# 2022-SS-ZT-2.net
KiCad netlist of a schematic drawn in EasyEDA Pro
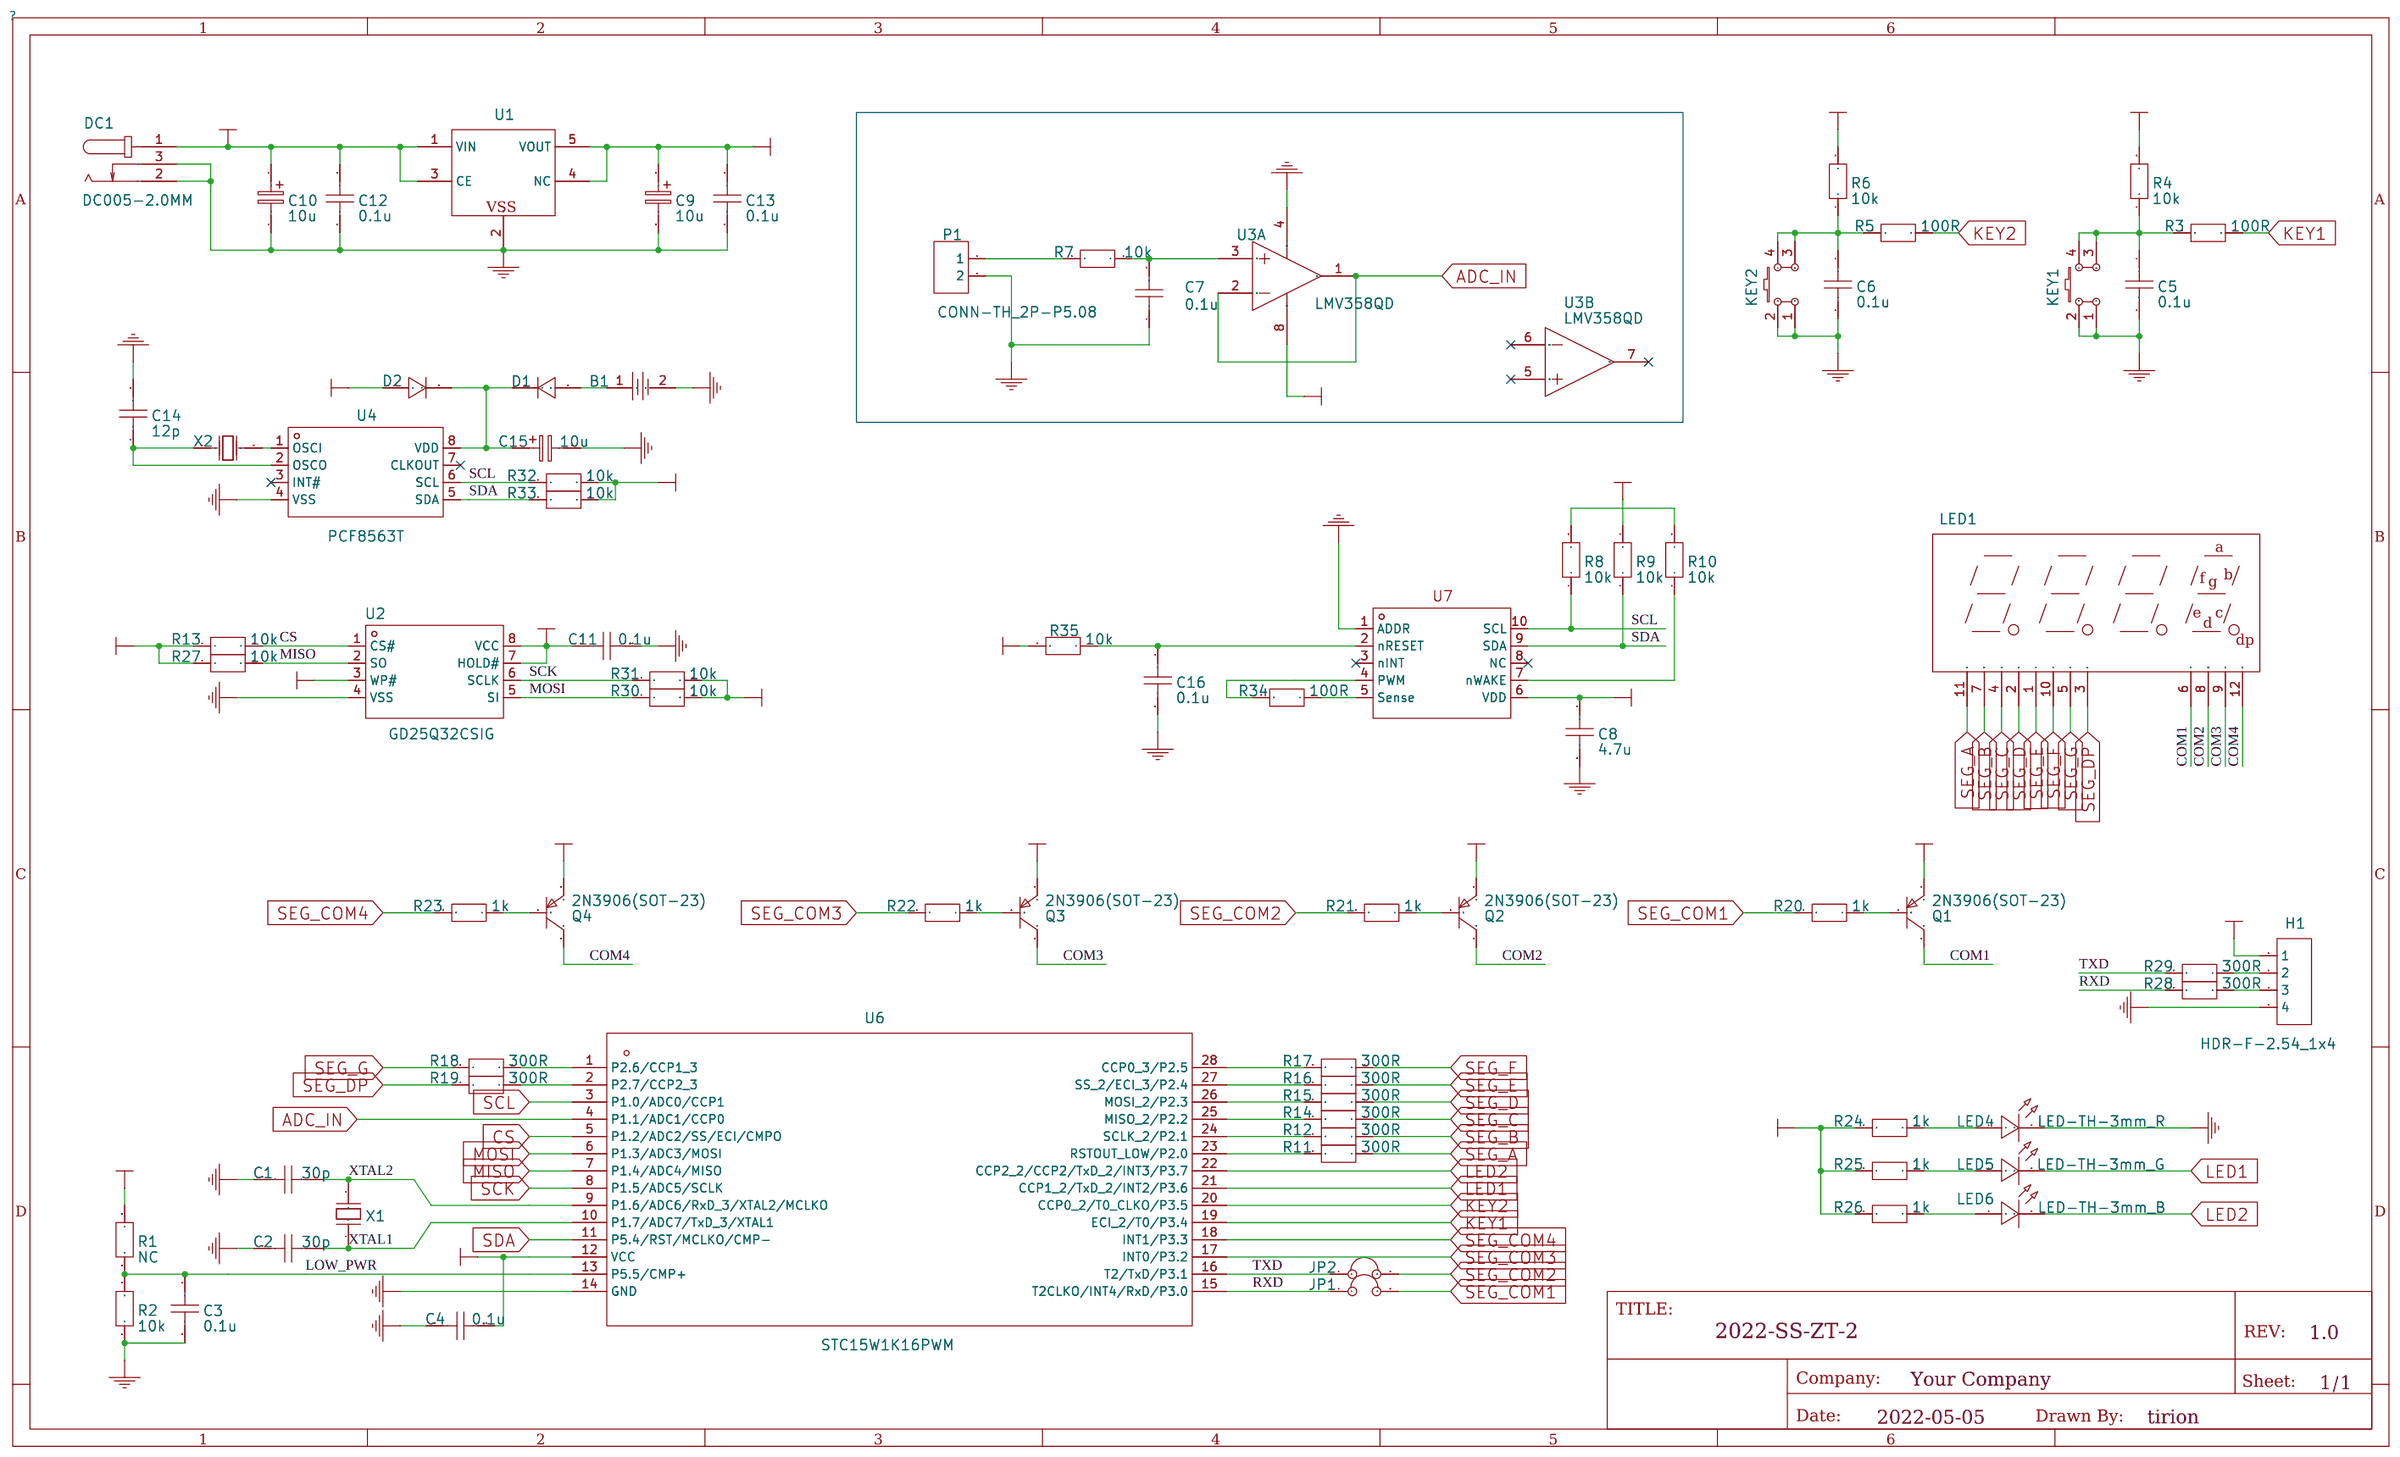
[diagram p0: schematic sheet]

(export (version "E")
  (design (tool "Eeschema 10.0.6"))
  (components
    (comp (ref "B1")
      (value "CR1220-2")
      (fields (field (name "Manufacturer") "Q&amp;J"))
      (libsource (lib "easyedapro") (part "CR1220-2"))
    )
    (comp (ref "C1") (value "30p") (libsource (lib "easyedapro") (part "30p")))
    (comp (ref "C2") (value "30p") (libsource (lib "easyedapro") (part "30p")))
    (comp (ref "C3") (value "0.1u") (libsource (lib "easyedapro") (part "0.1u")))
    (comp (ref "C4") (value "0.1u") (libsource (lib "easyedapro") (part "0.1u")))
    (comp (ref "C5") (value "0.1u") (libsource (lib "easyedapro") (part "0.1u")))
    (comp (ref "C6") (value "0.1u") (libsource (lib "easyedapro") (part "0.1u")))
    (comp (ref "C7") (value "0.1u") (libsource (lib "easyedapro") (part "0.1u")))
    (comp (ref "C8") (value "4.7u") (libsource (lib "easyedapro") (part "4.7u")))
    (comp (ref "C9") (value "10u") (libsource (lib "easyedapro") (part "10u")))
    (comp (ref "C10") (value "10u") (libsource (lib "easyedapro") (part "10u")))
    (comp (ref "C11") (value "0.1u") (libsource (lib "easyedapro") (part "0.1u")))
    (comp (ref "C12") (value "0.1u") (libsource (lib "easyedapro") (part "0.1u")))
    (comp (ref "C13") (value "0.1u") (libsource (lib "easyedapro") (part "0.1u")))
    (comp (ref "C14") (value "12p") (libsource (lib "easyedapro") (part "12p")))
    (comp (ref "C15") (value "10u") (libsource (lib "easyedapro") (part "10u")))
    (comp (ref "C16") (value "0.1u") (libsource (lib "easyedapro") (part "0.1u")))
    (comp (ref "D1")
      (value "1N4148")
      (fields (field (name "Manufacturer") "STMicroelectronics"))
      (libsource (lib "easyedapro") (part "1N4148"))
    )
    (comp (ref "D2")
      (value "1N4148")
      (fields (field (name "Manufacturer") "STMicroelectronics"))
      (libsource (lib "easyedapro") (part "1N4148"))
    )
    (comp (ref "DC1")
      (value "DC005-2.0MM")
      (fields (field (name "Manufacturer") "SOFNG"))
      (libsource (lib "easyedapro") (part "DC005-2.0MM"))
    )
    (comp (ref "H1") (value "HDR-F-2.54_1x4") (libsource (lib "easyedapro") (part "HDR-F-2.54_1x4")))
    (comp (ref "JP1") (value "跳线") (libsource (lib "easyedapro") (part "跳线")))
    (comp (ref "JP2") (value "跳线") (libsource (lib "easyedapro") (part "跳线")))
    (comp (ref "KEY1")
      (value "K4-6×6_SMD")
      (fields (field (name "Manufacturer Part") "K2-6639SP-D4SC-04") (field (name "Manufacturer") "韩国韩荣"))
      (libsource (lib "easyedapro") (part "K4-6×6_SMD"))
    )
    (comp (ref "KEY2")
      (value "K4-6×6_SMD")
      (fields (field (name "Manufacturer Part") "K2-6639SP-D4SC-04") (field (name "Manufacturer") "韩国韩荣"))
      (libsource (lib "easyedapro") (part "K4-6×6_SMD"))
    )
    (comp (ref "LED1")
      (value "0.36寸4位数码管")
      (fields (field (name "Manufacturer Part") "FJ5461BH 纯红") (field (name "Manufacturer") "ReliaPro"))
      (libsource (lib "easyedapro") (part "0.36寸4位数码管"))
    )
    (comp (ref "LED4")
      (value "LED-TH-3mm_R")
      (fields
        (field (name "Manufacturer Part") "204-10SDRD/S530-A3-L")
        (field (name "Manufacturer") "EVERLIGHT(台湾亿光)")
      )
      (libsource (lib "easyedapro") (part "LED-TH-3mm_R"))
    )
    (comp (ref "LED5")
      (value "LED-TH-3mm_G")
      (fields
        (field (name "Manufacturer Part") "204-10SYGD/S530-E3")
        (field (name "Manufacturer") "EVERLIGHT(台湾亿光)")
      )
      (libsource (lib "easyedapro") (part "LED-TH-3mm_G"))
    )
    (comp (ref "LED6")
      (value "LED-TH-3mm_B")
      (fields
        (field (name "Manufacturer Part") "204-10SUBC/S400-A4")
        (field (name "Manufacturer") "EVERLIGHT(台湾亿光)")
      )
      (libsource (lib "easyedapro") (part "LED-TH-3mm_B"))
    )
    (comp (ref "P1") (value "CONN-TH_2P-P5.08") (libsource (lib "easyedapro") (part "CONN-TH_2P-P5.08")))
    (comp (ref "Q1")
      (value "2N3906(SOT-23)")
      (fields (field (name "Manufacturer Part") "2N3906S-RTK/PS") (field (name "Manufacturer") "KEC"))
      (libsource (lib "easyedapro") (part "2N3906(SOT-23)"))
    )
    (comp (ref "Q2")
      (value "2N3906(SOT-23)")
      (fields (field (name "Manufacturer Part") "2N3906S-RTK/PS") (field (name "Manufacturer") "KEC"))
      (libsource (lib "easyedapro") (part "2N3906(SOT-23)"))
    )
    (comp (ref "Q3")
      (value "2N3906(SOT-23)")
      (fields (field (name "Manufacturer Part") "2N3906S-RTK/PS") (field (name "Manufacturer") "KEC"))
      (libsource (lib "easyedapro") (part "2N3906(SOT-23)"))
    )
    (comp (ref "Q4")
      (value "2N3906(SOT-23)")
      (fields (field (name "Manufacturer Part") "2N3906S-RTK/PS") (field (name "Manufacturer") "KEC"))
      (libsource (lib "easyedapro") (part "2N3906(SOT-23)"))
    )
    (comp (ref "R1") (value "NC") (libsource (lib "easyedapro") (part "NC")))
    (comp (ref "R2") (value "10k") (libsource (lib "easyedapro") (part "10k")))
    (comp (ref "R3") (value "100R") (libsource (lib "easyedapro") (part "100R")))
    (comp (ref "R4") (value "10k") (libsource (lib "easyedapro") (part "10k")))
    (comp (ref "R5") (value "100R") (libsource (lib "easyedapro") (part "100R")))
    (comp (ref "R6") (value "10k") (libsource (lib "easyedapro") (part "10k")))
    (comp (ref "R7") (value "10k") (libsource (lib "easyedapro") (part "10k")))
    (comp (ref "R8") (value "10k") (libsource (lib "easyedapro") (part "10k")))
    (comp (ref "R9") (value "10k") (libsource (lib "easyedapro") (part "10k")))
    (comp (ref "R10") (value "10k") (libsource (lib "easyedapro") (part "10k")))
    (comp (ref "R11") (value "300R") (libsource (lib "easyedapro") (part "300R")))
    (comp (ref "R12") (value "300R") (libsource (lib "easyedapro") (part "300R")))
    (comp (ref "R13") (value "10k") (libsource (lib "easyedapro") (part "10k")))
    (comp (ref "R14") (value "300R") (libsource (lib "easyedapro") (part "300R")))
    (comp (ref "R15") (value "300R") (libsource (lib "easyedapro") (part "300R")))
    (comp (ref "R16") (value "300R") (libsource (lib "easyedapro") (part "300R")))
    (comp (ref "R17") (value "300R") (libsource (lib "easyedapro") (part "300R")))
    (comp (ref "R18") (value "300R") (libsource (lib "easyedapro") (part "300R")))
    (comp (ref "R19") (value "300R") (libsource (lib "easyedapro") (part "300R")))
    (comp (ref "R20") (value "1k") (libsource (lib "easyedapro") (part "1k")))
    (comp (ref "R21") (value "1k") (libsource (lib "easyedapro") (part "1k")))
    (comp (ref "R22") (value "1k") (libsource (lib "easyedapro") (part "1k")))
    (comp (ref "R23") (value "1k") (libsource (lib "easyedapro") (part "1k")))
    (comp (ref "R24") (value "1k") (libsource (lib "easyedapro") (part "1k")))
    (comp (ref "R25") (value "1k") (libsource (lib "easyedapro") (part "1k")))
    (comp (ref "R26") (value "1k") (libsource (lib "easyedapro") (part "1k")))
    (comp (ref "R27") (value "10k") (libsource (lib "easyedapro") (part "10k")))
    (comp (ref "R28") (value "300R") (libsource (lib "easyedapro") (part "300R")))
    (comp (ref "R29") (value "300R") (libsource (lib "easyedapro") (part "300R")))
    (comp (ref "R30") (value "10k") (libsource (lib "easyedapro") (part "10k")))
    (comp (ref "R31") (value "10k") (libsource (lib "easyedapro") (part "10k")))
    (comp (ref "R32") (value "10k") (libsource (lib "easyedapro") (part "10k")))
    (comp (ref "R33") (value "10k") (libsource (lib "easyedapro") (part "10k")))
    (comp (ref "R34") (value "100R") (libsource (lib "easyedapro") (part "100R")))
    (comp (ref "R35") (value "10k") (libsource (lib "easyedapro") (part "10k")))
    (comp (ref "U1")
      (value "XC6210A252M")
      (fields (field (name "Manufacturer") "Torex Semicon"))
      (libsource (lib "easyedapro") (part "XC6210A252M"))
    )
    (comp (ref "U2")
      (value "GD25Q32CSIG")
      (fields (field (name "Manufacturer") "GigaDevice"))
      (libsource (lib "easyedapro") (part "GD25Q32CSIG"))
    )
    (comp (ref "U3")
      (value "LMV358QD")
      (fields (field (name "Manufacturer") "TI(德州仪器)"))
      (libsource (lib "easyedapro") (part "LMV358QD"))
    )
    (comp (ref "U4")
      (value "PCF8563T")
      (fields (field (name "Manufacturer Part") "PCF8563T/5,518") (field (name "Manufacturer") "NXP"))
      (libsource (lib "easyedapro") (part "PCF8563T"))
    )
    (comp (ref "U6")
      (value "STC15W1K16PWM")
      (fields (field (name "Manufacturer") "STC"))
      (libsource (lib "easyedapro") (part "STC15W1K16PWM"))
    )
    (comp (ref "U7") (value "SOIC-10") (libsource (lib "easyedapro") (part "SOIC-10")))
    (comp (ref "X1")
      (value "12MHZ")
      (fields (field (name "Manufacturer Part") "X49UD12MSD2SC") (field (name "Manufacturer") "LCSC"))
      (libsource (lib "easyedapro") (part "12MHZ"))
    )
    (comp (ref "X2")
      (value "32.768KHz")
      (fields
        (field (name "Manufacturer Part") "6K832768F12UB")
        (field (name "Manufacturer") "SHENZHEN CRYSTAL TECH")
      )
      (libsource (lib "easyedapro") (part "32.768KHz"))
    )
  )
  (nets
    (net (code "1") (name "/COM1") (class "Default")
      (node (ref "LED1") (pin "6") (pinfunction "DIG4_6") (pintype "input"))
      (node (ref "Q1") (pin "3") (pinfunction "C_3") (pintype "input"))
    )
    (net (code "2") (name "/COM2") (class "Default")
      (node (ref "LED1") (pin "8") (pinfunction "DIG3_8") (pintype "input"))
      (node (ref "Q2") (pin "3") (pinfunction "C_3") (pintype "input"))
    )
    (net (code "3") (name "/COM3") (class "Default")
      (node (ref "LED1") (pin "9") (pinfunction "DIG2_9") (pintype "input"))
      (node (ref "Q3") (pin "3") (pinfunction "C_3") (pintype "input"))
    )
    (net (code "4") (name "/COM4") (class "Default")
      (node (ref "LED1") (pin "12") (pinfunction "DIG1_12") (pintype "input"))
      (node (ref "Q4") (pin "3") (pinfunction "C_3") (pintype "input"))
    )
    (net (code "5") (name "/LOW_PWR") (class "Default")
      (node (ref "C3") (pin "1") (pinfunction "1_1") (pintype "input"))
      (node (ref "R1") (pin "1") (pinfunction "1_1") (pintype "input"))
      (node (ref "R2") (pin "2") (pinfunction "2_2") (pintype "input"))
      (node (ref "U6") (pin "13") (pinfunction "P5.5/CMP+_13") (pintype "input"))
    )
    (net (code "6") (name "/RXD") (class "Default")
      (node (ref "JP1") (pin "1") (pinfunction "1_1") (pintype "input"))
      (node (ref "R28") (pin "2") (pinfunction "2_2") (pintype "input"))
      (node (ref "U6") (pin "15") (pinfunction "T2CLKO/INT4/RxD/P3.0_15") (pintype "input"))
    )
    (net (code "7") (name "/TXD") (class "Default")
      (node (ref "JP2") (pin "1") (pinfunction "1_1") (pintype "input"))
      (node (ref "R29") (pin "2") (pinfunction "2_2") (pintype "input"))
      (node (ref "U6") (pin "16") (pinfunction "T2/TxD/P3.1_16") (pintype "input"))
    )
    (net (code "8") (name "/XTAL1") (class "Default")
      (node (ref "C2") (pin "1") (pinfunction "1_1") (pintype "input"))
      (node (ref "U6") (pin "10") (pinfunction "P1.7/ADC7/TxD_3/XTAL1_10") (pintype "input"))
      (node (ref "X1") (pin "1") (pinfunction "OSC1_1") (pintype "input"))
    )
    (net (code "9") (name "/XTAL2") (class "Default")
      (node (ref "C1") (pin "1") (pinfunction "1_1") (pintype "input"))
      (node (ref "U6") (pin "9") (pinfunction "P1.6/ADC6/RxD_3/XTAL2/MCLKO_9") (pintype "input"))
      (node (ref "X1") (pin "2") (pinfunction "OSC2_2") (pintype "input"))
    )
    (net (code "10") (name "ADC_IN") (class "Default")
      (node (ref "U3") (pin "1") (pinfunction "OUT_1") (pintype "output"))
      (node (ref "U3") (pin "2") (pinfunction "1IN-_2") (pintype "input"))
      (node (ref "U6") (pin "4") (pinfunction "P1.1/ADC1/CCP0_4") (pintype "input"))
    )
    (net (code "11") (name "CS") (class "Default")
      (node (ref "R13") (pin "2") (pinfunction "2_2") (pintype "input"))
      (node (ref "U2") (pin "1") (pinfunction "CS#_1") (pintype "input"))
      (node (ref "U6") (pin "5") (pinfunction "P1.2/ADC2/SS/ECI/CMPO_5") (pintype "input"))
    )
    (net (code "12") (name "DC") (class "Default")
      (node (ref "C10") (pin "1") (pinfunction "1_1") (pintype "input"))
      (node (ref "C12") (pin "1") (pinfunction "1_1") (pintype "input"))
      (node (ref "DC1") (pin "1") (pinfunction "1_1") (pintype "input"))
      (node (ref "R1") (pin "2") (pinfunction "2_2") (pintype "input"))
      (node (ref "U1") (pin "1") (pinfunction "VIN_1") (pintype "input"))
      (node (ref "U1") (pin "3") (pinfunction "CE_3") (pintype "input"))
    )
    (net (code "13") (name "GND") (class "Default")
      (node (ref "B1") (pin "2") (pinfunction "2_2") (pintype "input"))
      (node (ref "C1") (pin "2") (pinfunction "2_2") (pintype "input"))
      (node (ref "C10") (pin "2") (pinfunction "2_2") (pintype "input"))
      (node (ref "C11") (pin "2") (pinfunction "2_2") (pintype "input"))
      (node (ref "C12") (pin "2") (pinfunction "2_2") (pintype "input"))
      (node (ref "C13") (pin "2") (pinfunction "2_2") (pintype "input"))
      (node (ref "C14") (pin "1") (pinfunction "1_1") (pintype "input"))
      (node (ref "C15") (pin "2") (pinfunction "2_2") (pintype "input"))
      (node (ref "C16") (pin "2") (pinfunction "2_2") (pintype "input"))
      (node (ref "C2") (pin "2") (pinfunction "2_2") (pintype "input"))
      (node (ref "C3") (pin "2") (pinfunction "2_2") (pintype "input"))
      (node (ref "C4") (pin "2") (pinfunction "2_2") (pintype "input"))
      (node (ref "C5") (pin "2") (pinfunction "2_2") (pintype "input"))
      (node (ref "C6") (pin "2") (pinfunction "2_2") (pintype "input"))
      (node (ref "C7") (pin "1") (pinfunction "1_1") (pintype "input"))
      (node (ref "C8") (pin "2") (pinfunction "2_2") (pintype "input"))
      (node (ref "C9") (pin "2") (pinfunction "2_2") (pintype "input"))
      (node (ref "DC1") (pin "2") (pinfunction "2_2") (pintype "input"))
      (node (ref "DC1") (pin "3") (pinfunction "3_3") (pintype "input"))
      (node (ref "H1") (pin "4") (pinfunction "4_4") (pintype "input"))
      (node (ref "KEY1") (pin "1") (pinfunction "1_1") (pintype "input"))
      (node (ref "KEY1") (pin "2") (pinfunction "2_2") (pintype "input"))
      (node (ref "KEY2") (pin "1") (pinfunction "1_1") (pintype "input"))
      (node (ref "KEY2") (pin "2") (pinfunction "2_2") (pintype "input"))
      (node (ref "LED4") (pin "2") (pinfunction "2_2") (pintype "input"))
      (node (ref "P1") (pin "2") (pinfunction "2_2") (pintype "input"))
      (node (ref "R2") (pin "1") (pinfunction "1_1") (pintype "input"))
      (node (ref "U1") (pin "2") (pinfunction "VSS_2") (pintype "input"))
      (node (ref "U2") (pin "4") (pinfunction "VSS_4") (pintype "input"))
      (node (ref "U3") (pin "4") (pinfunction "GND_4") (pintype "input"))
      (node (ref "U4") (pin "4") (pinfunction "VSS_4") (pintype "input"))
      (node (ref "U6") (pin "14") (pinfunction "GND_14") (pintype "input"))
      (node (ref "U7") (pin "1") (pinfunction "ADDR_1") (pintype "input"))
    )
    (net (code "14") (name "KEY1") (class "Default")
      (node (ref "R3") (pin "1") (pinfunction "1_1") (pintype "input"))
      (node (ref "U6") (pin "19") (pinfunction "ECI_2/T0/P3.4_19") (pintype "input"))
    )
    (net (code "15") (name "KEY2") (class "Default")
      (node (ref "R5") (pin "1") (pinfunction "1_1") (pintype "input"))
      (node (ref "U6") (pin "20") (pinfunction "CCP0_2/T0_CLKO/P3.5_20") (pintype "input"))
    )
    (net (code "16") (name "LED1") (class "Default")
      (node (ref "LED5") (pin "2") (pinfunction "2_2") (pintype "input"))
      (node (ref "U6") (pin "21") (pinfunction "CCP1_2/TxD_2/INT2/P3.6_21") (pintype "input"))
    )
    (net (code "17") (name "LED2") (class "Default")
      (node (ref "LED6") (pin "2") (pinfunction "2_2") (pintype "input"))
      (node (ref "U6") (pin "22") (pinfunction "CCP2_2/CCP2/TxD_2/INT3/P3.7_22") (pintype "input"))
    )
    (net (code "18") (name "MISO") (class "Default")
      (node (ref "R27") (pin "2") (pinfunction "2_2") (pintype "input"))
      (node (ref "U2") (pin "2") (pinfunction "SO_2") (pintype "input"))
      (node (ref "U6") (pin "7") (pinfunction "P1.4/ADC4/MISO_7") (pintype "input"))
    )
    (net (code "19") (name "MOSI") (class "Default")
      (node (ref "R30") (pin "1") (pinfunction "1_1") (pintype "input"))
      (node (ref "U2") (pin "5") (pinfunction "SI_5") (pintype "input"))
      (node (ref "U6") (pin "6") (pinfunction "P1.3/ADC3/MOSI_6") (pintype "input"))
    )
    (net (code "20") (name "Net-(B1-Pad1)") (class "Default")
      (node (ref "B1") (pin "1") (pinfunction "1_1") (pintype "input"))
      (node (ref "D1") (pin "2") (pinfunction "2_2") (pintype "input"))
    )
    (net (code "21") (name "Net-(C5-Pad1)") (class "Default")
      (node (ref "C5") (pin "1") (pinfunction "1_1") (pintype "input"))
      (node (ref "KEY1") (pin "3") (pinfunction "3_3") (pintype "input"))
      (node (ref "KEY1") (pin "4") (pinfunction "4_4") (pintype "input"))
      (node (ref "R3") (pin "2") (pinfunction "2_2") (pintype "input"))
      (node (ref "R4") (pin "1") (pinfunction "1_1") (pintype "input"))
    )
    (net (code "22") (name "Net-(C6-Pad1)") (class "Default")
      (node (ref "C6") (pin "1") (pinfunction "1_1") (pintype "input"))
      (node (ref "KEY2") (pin "3") (pinfunction "3_3") (pintype "input"))
      (node (ref "KEY2") (pin "4") (pinfunction "4_4") (pintype "input"))
      (node (ref "R5") (pin "2") (pinfunction "2_2") (pintype "input"))
      (node (ref "R6") (pin "1") (pinfunction "1_1") (pintype "input"))
    )
    (net (code "23") (name "Net-(H1-Pad2)") (class "Default")
      (node (ref "H1") (pin "2") (pinfunction "2_2") (pintype "input"))
      (node (ref "R29") (pin "1") (pinfunction "1_1") (pintype "input"))
    )
    (net (code "24") (name "Net-(H1-Pad3)") (class "Default")
      (node (ref "H1") (pin "3") (pinfunction "3_3") (pintype "input"))
      (node (ref "R28") (pin "1") (pinfunction "1_1") (pintype "input"))
    )
    (net (code "25") (name "Net-(LED4-Pad1)") (class "Default")
      (node (ref "LED4") (pin "1") (pinfunction "1_1") (pintype "input"))
      (node (ref "R24") (pin "1") (pinfunction "1_1") (pintype "input"))
    )
    (net (code "26") (name "Net-(LED5-Pad1)") (class "Default")
      (node (ref "LED5") (pin "1") (pinfunction "1_1") (pintype "input"))
      (node (ref "R25") (pin "1") (pinfunction "1_1") (pintype "input"))
    )
    (net (code "27") (name "Net-(LED6-Pad1)") (class "Default")
      (node (ref "LED6") (pin "1") (pinfunction "1_1") (pintype "input"))
      (node (ref "R26") (pin "1") (pinfunction "1_1") (pintype "input"))
    )
    (net (code "28") (name "Net-(P1-Pad1)") (class "Default")
      (node (ref "P1") (pin "1") (pinfunction "1_1") (pintype "input"))
      (node (ref "R7") (pin "2") (pinfunction "2_2") (pintype "input"))
    )
    (net (code "29") (name "Net-(Q1-B)") (class "Default")
      (node (ref "Q1") (pin "2") (pinfunction "B_2") (pintype "input"))
      (node (ref "R20") (pin "1") (pinfunction "1_1") (pintype "input"))
    )
    (net (code "30") (name "Net-(Q2-B)") (class "Default")
      (node (ref "Q2") (pin "2") (pinfunction "B_2") (pintype "input"))
      (node (ref "R21") (pin "1") (pinfunction "1_1") (pintype "input"))
    )
    (net (code "31") (name "Net-(Q3-B)") (class "Default")
      (node (ref "Q3") (pin "2") (pinfunction "B_2") (pintype "input"))
      (node (ref "R22") (pin "1") (pinfunction "1_1") (pintype "input"))
    )
    (net (code "32") (name "Net-(Q4-B)") (class "Default")
      (node (ref "Q4") (pin "2") (pinfunction "B_2") (pintype "input"))
      (node (ref "R23") (pin "1") (pinfunction "1_1") (pintype "input"))
    )
    (net (code "33") (name "Net-(R10-Pad2)") (class "Default")
      (node (ref "R10") (pin "2") (pinfunction "2_2") (pintype "input"))
      (node (ref "R8") (pin "2") (pinfunction "2_2") (pintype "input"))
    )
    (net (code "34") (name "Net-(U3A-1IN+)") (class "Default")
      (node (ref "C7") (pin "2") (pinfunction "2_2") (pintype "input"))
      (node (ref "R7") (pin "1") (pinfunction "1_1") (pintype "input"))
      (node (ref "U3") (pin "3") (pinfunction "1IN+_3") (pintype "input"))
    )
    (net (code "35") (name "Net-(U4-OSCI)") (class "Default")
      (node (ref "U4") (pin "1") (pinfunction "OSCI_1") (pintype "input"))
      (node (ref "X2") (pin "2") (pinfunction "OSC2_2") (pintype "input"))
    )
    (net (code "36") (name "Net-(U4-OSCO)") (class "Default")
      (node (ref "C14") (pin "2") (pinfunction "2_2") (pintype "input"))
      (node (ref "U4") (pin "2") (pinfunction "OSCO_2") (pintype "input"))
      (node (ref "X2") (pin "1") (pinfunction "OSC1_1") (pintype "input"))
    )
    (net (code "37") (name "Net-(U4-VDD)") (class "Default")
      (node (ref "C15") (pin "1") (pinfunction "1_1") (pintype "input"))
      (node (ref "D1") (pin "1") (pinfunction "1_1") (pintype "input"))
      (node (ref "D2") (pin "1") (pinfunction "1_1") (pintype "input"))
      (node (ref "U4") (pin "8") (pinfunction "VDD_8") (pintype "input"))
    )
    (net (code "38") (name "Net-(U6-CCP0_3{slash}P2.5)") (class "Default")
      (node (ref "R17") (pin "2") (pinfunction "2_2") (pintype "input"))
      (node (ref "U6") (pin "28") (pinfunction "CCP0_3/P2.5_28") (pintype "input"))
    )
    (net (code "39") (name "Net-(U6-MISO_2{slash}P2.2)") (class "Default")
      (node (ref "R14") (pin "2") (pinfunction "2_2") (pintype "input"))
      (node (ref "U6") (pin "25") (pinfunction "MISO_2/P2.2_25") (pintype "input"))
    )
    (net (code "40") (name "Net-(U6-MOSI_2{slash}P2.3)") (class "Default")
      (node (ref "R15") (pin "2") (pinfunction "2_2") (pintype "input"))
      (node (ref "U6") (pin "26") (pinfunction "MOSI_2/P2.3_26") (pintype "input"))
    )
    (net (code "41") (name "Net-(U6-P2.6{slash}CCP1_3)") (class "Default")
      (node (ref "R18") (pin "1") (pinfunction "1_1") (pintype "input"))
      (node (ref "U6") (pin "1") (pinfunction "P2.6/CCP1_3_1") (pintype "input"))
    )
    (net (code "42") (name "Net-(U6-P2.7{slash}CCP2_3)") (class "Default")
      (node (ref "R19") (pin "1") (pinfunction "1_1") (pintype "input"))
      (node (ref "U6") (pin "2") (pinfunction "P2.7/CCP2_3_2") (pintype "input"))
    )
    (net (code "43") (name "Net-(U6-RSTOUT_LOW{slash}P2.0)") (class "Default")
      (node (ref "R11") (pin "2") (pinfunction "2_2") (pintype "input"))
      (node (ref "U6") (pin "23") (pinfunction "RSTOUT_LOW/P2.0_23") (pintype "input"))
    )
    (net (code "44") (name "Net-(U6-SCLK_2{slash}P2.1)") (class "Default")
      (node (ref "R12") (pin "2") (pinfunction "2_2") (pintype "input"))
      (node (ref "U6") (pin "24") (pinfunction "SCLK_2/P2.1_24") (pintype "input"))
    )
    (net (code "45") (name "Net-(U6-SS_2{slash}ECI_3{slash}P2.4)") (class "Default")
      (node (ref "R16") (pin "2") (pinfunction "2_2") (pintype "input"))
      (node (ref "U6") (pin "27") (pinfunction "SS_2/ECI_3/P2.4_27") (pintype "input"))
    )
    (net (code "46") (name "Net-(U7-PWM)") (class "Default")
      (node (ref "R34") (pin "2") (pinfunction "2_2") (pintype "input"))
      (node (ref "U7") (pin "4") (pinfunction "PWM_4") (pintype "input"))
    )
    (net (code "47") (name "Net-(U7-Sense)") (class "Default")
      (node (ref "R34") (pin "1") (pinfunction "1_1") (pintype "input"))
      (node (ref "U7") (pin "5") (pinfunction "Sense_5") (pintype "input"))
    )
    (net (code "48") (name "Net-(U7-nRESET)") (class "Default")
      (node (ref "C16") (pin "1") (pinfunction "1_1") (pintype "input"))
      (node (ref "R35") (pin "1") (pinfunction "1_1") (pintype "input"))
      (node (ref "U7") (pin "2") (pinfunction "nRESET_2") (pintype "input"))
    )
    (net (code "49") (name "Net-(U7-nWAKE)") (class "Default")
      (node (ref "R10") (pin "1") (pinfunction "1_1") (pintype "input"))
      (node (ref "U7") (pin "7") (pinfunction "nWAKE_7") (pintype "input"))
    )
    (net (code "50") (name "SCK") (class "Default")
      (node (ref "R31") (pin "1") (pinfunction "1_1") (pintype "input"))
      (node (ref "U2") (pin "6") (pinfunction "SCLK_6") (pintype "input"))
      (node (ref "U6") (pin "8") (pinfunction "P1.5/ADC5/SCLK_8") (pintype "input"))
    )
    (net (code "51") (name "SCL") (class "Default")
      (node (ref "R32") (pin "1") (pinfunction "1_1") (pintype "input"))
      (node (ref "R8") (pin "1") (pinfunction "1_1") (pintype "input"))
      (node (ref "U4") (pin "6") (pinfunction "SCL_6") (pintype "input"))
      (node (ref "U6") (pin "3") (pinfunction "P1.0/ADC0/CCP1_3") (pintype "input"))
      (node (ref "U7") (pin "10") (pinfunction "SCL_10") (pintype "input"))
    )
    (net (code "52") (name "SDA") (class "Default")
      (node (ref "R33") (pin "1") (pinfunction "1_1") (pintype "input"))
      (node (ref "R9") (pin "1") (pinfunction "1_1") (pintype "input"))
      (node (ref "U4") (pin "5") (pinfunction "SDA_5") (pintype "input"))
      (node (ref "U6") (pin "11") (pinfunction "P5.4/RST/MCLKO/CMP-_11") (pintype "input"))
      (node (ref "U7") (pin "9") (pinfunction "SDA_9") (pintype "input"))
    )
    (net (code "53") (name "SEG_A") (class "Default")
      (node (ref "LED1") (pin "11") (pinfunction "A_11") (pintype "input"))
      (node (ref "R11") (pin "1") (pinfunction "1_1") (pintype "input"))
    )
    (net (code "54") (name "SEG_B") (class "Default")
      (node (ref "LED1") (pin "7") (pinfunction "B_7") (pintype "input"))
      (node (ref "R12") (pin "1") (pinfunction "1_1") (pintype "input"))
    )
    (net (code "55") (name "SEG_C") (class "Default")
      (node (ref "LED1") (pin "4") (pinfunction "C_4") (pintype "input"))
      (node (ref "R14") (pin "1") (pinfunction "1_1") (pintype "input"))
    )
    (net (code "56") (name "SEG_COM1") (class "Default")
      (node (ref "JP1") (pin "2") (pinfunction "2_2") (pintype "input"))
      (node (ref "R20") (pin "2") (pinfunction "2_2") (pintype "input"))
    )
    (net (code "57") (name "SEG_COM2") (class "Default")
      (node (ref "JP2") (pin "2") (pinfunction "2_2") (pintype "input"))
      (node (ref "R21") (pin "2") (pinfunction "2_2") (pintype "input"))
    )
    (net (code "58") (name "SEG_COM3") (class "Default")
      (node (ref "R22") (pin "2") (pinfunction "2_2") (pintype "input"))
      (node (ref "U6") (pin "17") (pinfunction "INT0/P3.2_17") (pintype "input"))
    )
    (net (code "59") (name "SEG_COM4") (class "Default")
      (node (ref "R23") (pin "2") (pinfunction "2_2") (pintype "input"))
      (node (ref "U6") (pin "18") (pinfunction "INT1/P3.3_18") (pintype "input"))
    )
    (net (code "60") (name "SEG_D") (class "Default")
      (node (ref "LED1") (pin "2") (pinfunction "D_2") (pintype "input"))
      (node (ref "R15") (pin "1") (pinfunction "1_1") (pintype "input"))
    )
    (net (code "61") (name "SEG_DP") (class "Default")
      (node (ref "LED1") (pin "3") (pinfunction "DP_3") (pintype "input"))
      (node (ref "R19") (pin "2") (pinfunction "2_2") (pintype "input"))
    )
    (net (code "62") (name "SEG_E") (class "Default")
      (node (ref "LED1") (pin "1") (pinfunction "E_1") (pintype "input"))
      (node (ref "R16") (pin "1") (pinfunction "1_1") (pintype "input"))
    )
    (net (code "63") (name "SEG_F") (class "Default")
      (node (ref "LED1") (pin "10") (pinfunction "F_10") (pintype "input"))
      (node (ref "R17") (pin "1") (pinfunction "1_1") (pintype "input"))
    )
    (net (code "64") (name "SEG_G") (class "Default")
      (node (ref "LED1") (pin "5") (pinfunction "G_5") (pintype "input"))
      (node (ref "R18") (pin "2") (pinfunction "2_2") (pintype "input"))
    )
    (net (code "65") (name "VDD") (class "Default")
      (node (ref "C11") (pin "1") (pinfunction "1_1") (pintype "input"))
      (node (ref "C13") (pin "1") (pinfunction "1_1") (pintype "input"))
      (node (ref "C4") (pin "1") (pinfunction "1_1") (pintype "input"))
      (node (ref "C8") (pin "1") (pinfunction "1_1") (pintype "input"))
      (node (ref "C9") (pin "1") (pinfunction "1_1") (pintype "input"))
      (node (ref "D2") (pin "2") (pinfunction "2_2") (pintype "input"))
      (node (ref "H1") (pin "1") (pinfunction "1_1") (pintype "input"))
      (node (ref "Q1") (pin "1") (pinfunction "E_1") (pintype "input"))
      (node (ref "Q2") (pin "1") (pinfunction "E_1") (pintype "input"))
      (node (ref "Q3") (pin "1") (pinfunction "E_1") (pintype "input"))
      (node (ref "Q4") (pin "1") (pinfunction "E_1") (pintype "input"))
      (node (ref "R13") (pin "1") (pinfunction "1_1") (pintype "input"))
      (node (ref "R24") (pin "2") (pinfunction "2_2") (pintype "input"))
      (node (ref "R25") (pin "2") (pinfunction "2_2") (pintype "input"))
      (node (ref "R26") (pin "2") (pinfunction "2_2") (pintype "input"))
      (node (ref "R27") (pin "1") (pinfunction "1_1") (pintype "input"))
      (node (ref "R30") (pin "2") (pinfunction "2_2") (pintype "input"))
      (node (ref "R31") (pin "2") (pinfunction "2_2") (pintype "input"))
      (node (ref "R32") (pin "2") (pinfunction "2_2") (pintype "input"))
      (node (ref "R33") (pin "2") (pinfunction "2_2") (pintype "input"))
      (node (ref "R35") (pin "2") (pinfunction "2_2") (pintype "input"))
      (node (ref "R4") (pin "2") (pinfunction "2_2") (pintype "input"))
      (node (ref "R6") (pin "2") (pinfunction "2_2") (pintype "input"))
      (node (ref "R9") (pin "2") (pinfunction "2_2") (pintype "input"))
      (node (ref "U1") (pin "4") (pinfunction "NC_4") (pintype "input"))
      (node (ref "U1") (pin "5") (pinfunction "VOUT_5") (pintype "input"))
      (node (ref "U2") (pin "3") (pinfunction "WP#_3") (pintype "input"))
      (node (ref "U2") (pin "7") (pinfunction "HOLD#_7") (pintype "input"))
      (node (ref "U2") (pin "8") (pinfunction "VCC_8") (pintype "input"))
      (node (ref "U3") (pin "8") (pinfunction "VCC+_8") (pintype "input"))
      (node (ref "U6") (pin "12") (pinfunction "VCC_12") (pintype "input"))
      (node (ref "U7") (pin "6") (pinfunction "VDD_6") (pintype "input"))
    )
    (net (code "66") (name "unconnected-(U3B-2IN+-Pad5)") (class "Default")
      (node (ref "U3") (pin "5") (pinfunction "2IN+_5") (pintype "input+no_connect"))
    )
    (net (code "67") (name "unconnected-(U3B-2IN--Pad6)") (class "Default")
      (node (ref "U3") (pin "6") (pinfunction "2IN-_6") (pintype "input+no_connect"))
    )
    (net (code "68") (name "unconnected-(U3B-2OUT-Pad7)") (class "Default")
      (node (ref "U3") (pin "7") (pinfunction "2OUT_7") (pintype "output+no_connect"))
    )
    (net (code "69") (name "unconnected-(U4-CLKOUT-Pad7)") (class "Default")
      (node (ref "U4") (pin "7") (pinfunction "CLKOUT_7") (pintype "input+no_connect"))
    )
    (net (code "70") (name "unconnected-(U4-INT#-Pad3)") (class "Default")
      (node (ref "U4") (pin "3") (pinfunction "INT#_3") (pintype "input+no_connect"))
    )
    (net (code "71") (name "unconnected-(U7-NC-Pad8)") (class "Default")
      (node (ref "U7") (pin "8") (pinfunction "NC_8") (pintype "input+no_connect"))
    )
    (net (code "72") (name "unconnected-(U7-nINT-Pad3)") (class "Default")
      (node (ref "U7") (pin "3") (pinfunction "nINT_3") (pintype "input+no_connect"))
    )
  )
)
